# sawbench_analog_reva.net
KiCad netlist of a schematic drawn in EAGLE
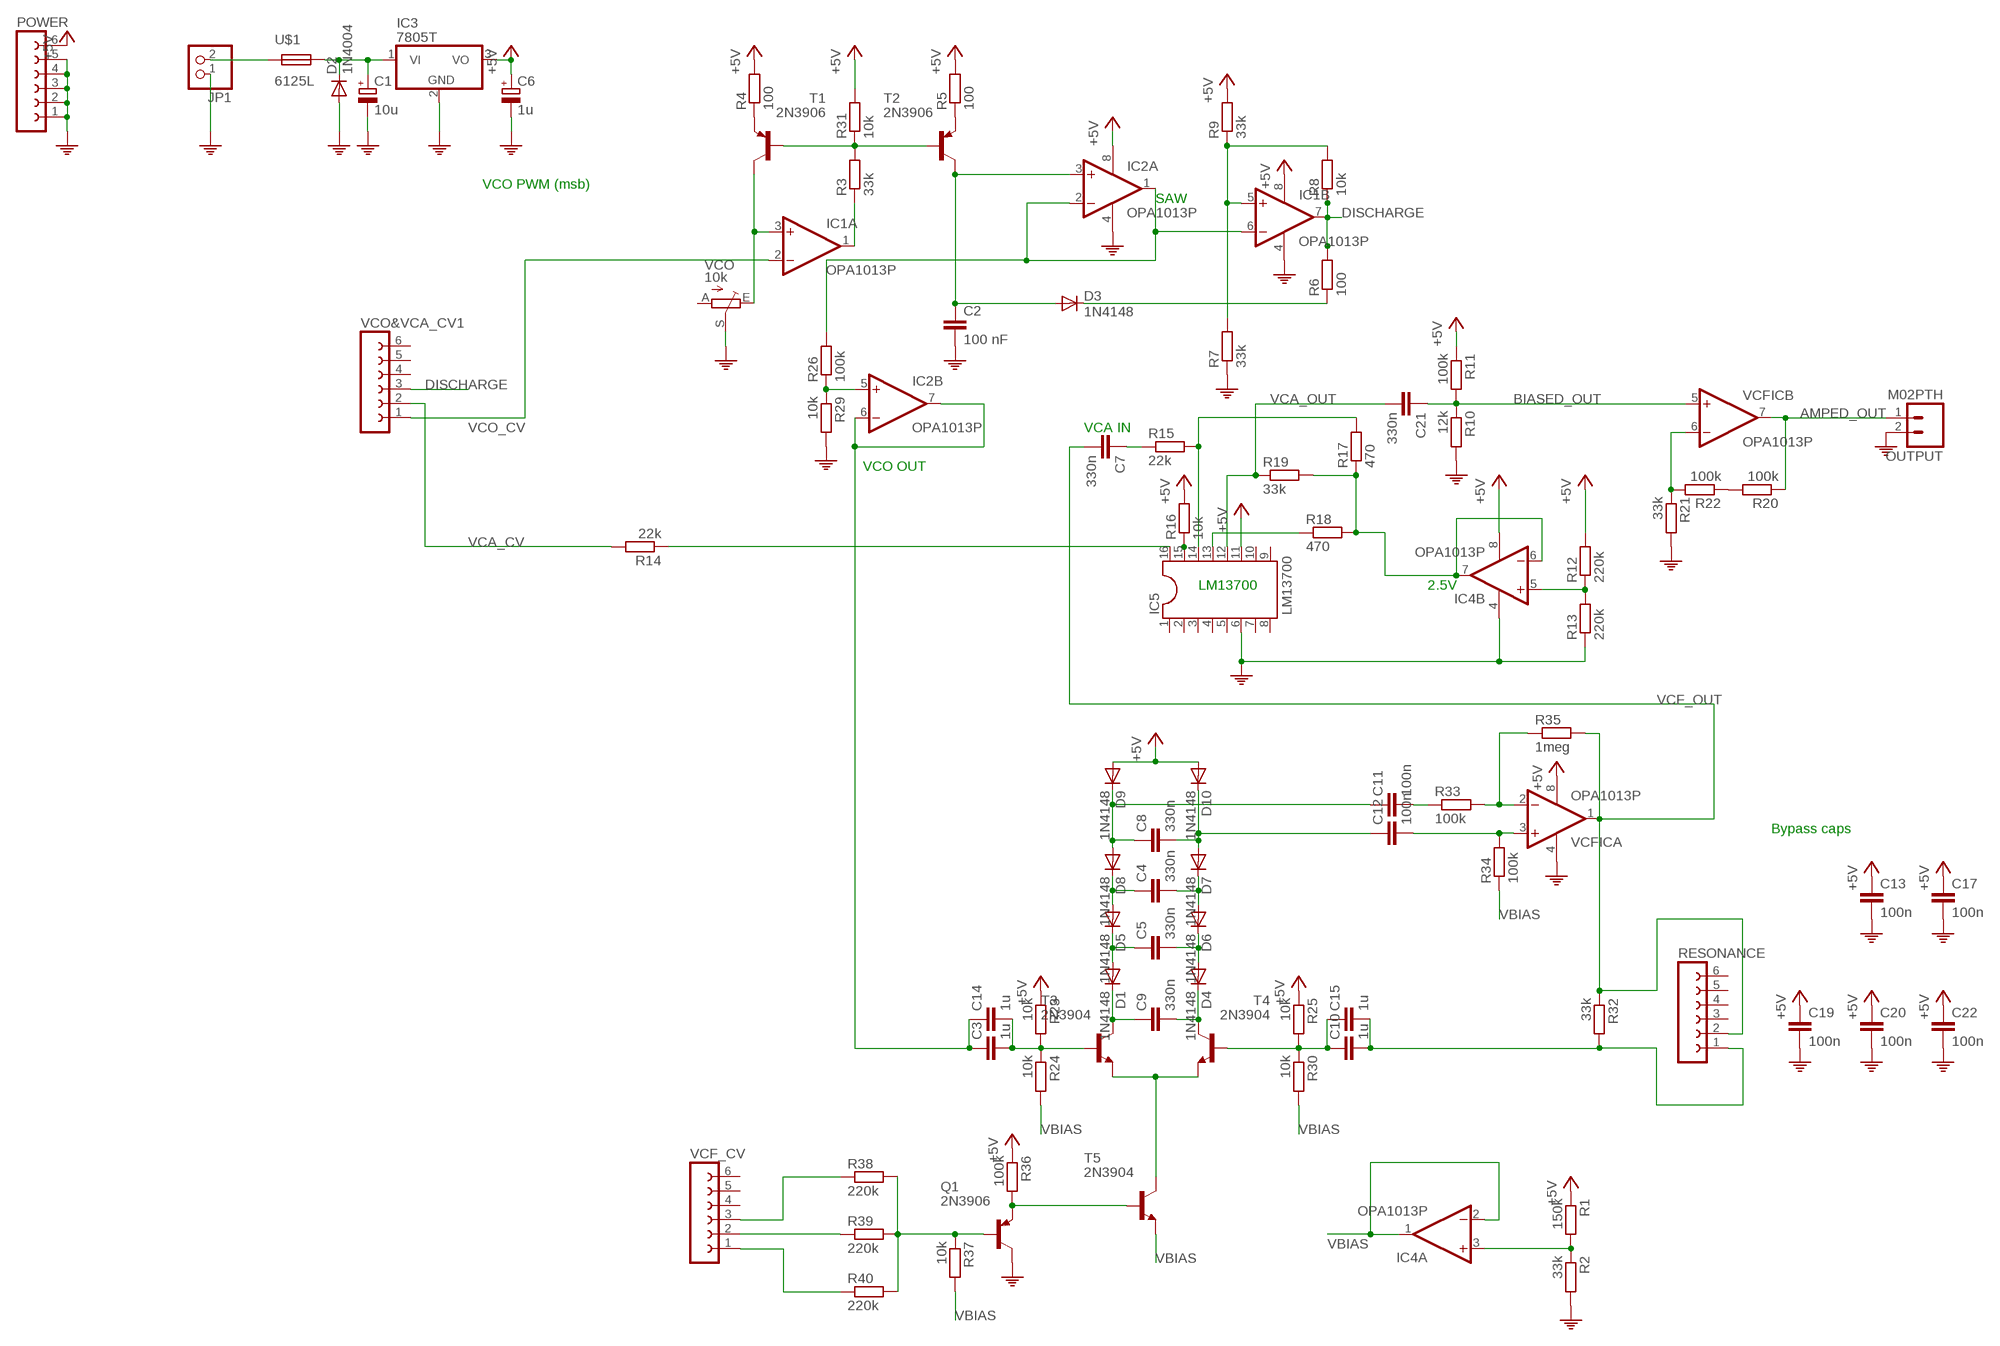
[diagram p0: schematic, sheet 1]

(export (version "E")
  (design (tool "Eeschema 10.0.6"))
  (components
    (comp (ref "C1")
      (value "10u")
      (footprint "eagle-import:E2,5-6")
      (libsource (lib "eagle-import") (part "CPOL-EUE2.5-6"))
    )
    (comp (ref "C2")
      (value "100 nF")
      (footprint "eagle-import:C050-030X075")
      (libsource (lib "eagle-import") (part "resistor_C-EU050-030X075"))
    )
    (comp (ref "C3")
      (value "1u")
      (footprint "eagle-import:C050-024X044")
      (libsource (lib "eagle-import") (part "resistor_C-EU050-024X044"))
    )
    (comp (ref "C4")
      (value "330n")
      (footprint "eagle-import:C050-030X075")
      (libsource (lib "eagle-import") (part "C-EU050-030X075"))
    )
    (comp (ref "C5")
      (value "330n")
      (footprint "eagle-import:C050-030X075")
      (libsource (lib "eagle-import") (part "C-EU050-030X075"))
    )
    (comp (ref "C6")
      (value "1u")
      (footprint "eagle-import:E2,5-6")
      (libsource (lib "eagle-import") (part "CPOL-EUE2.5-6"))
    )
    (comp (ref "C7")
      (value "330n")
      (footprint "eagle-import:C050-024X044")
      (libsource (lib "eagle-import") (part "resistor_C-EU050-024X044"))
    )
    (comp (ref "C8")
      (value "330n")
      (footprint "eagle-import:C050-030X075")
      (libsource (lib "eagle-import") (part "C-EU050-030X075"))
    )
    (comp (ref "C9")
      (value "330n")
      (footprint "eagle-import:C050-030X075")
      (libsource (lib "eagle-import") (part "C-EU050-030X075"))
    )
    (comp (ref "C10")
      (value "1u")
      (footprint "eagle-import:C050-024X044")
      (libsource (lib "eagle-import") (part "resistor_C-EU050-024X044"))
    )
    (comp (ref "C11")
      (value "100n")
      (footprint "eagle-import:C050-025X075")
      (libsource (lib "eagle-import") (part "resistor_C-EU050-025X075"))
    )
    (comp (ref "C12")
      (value "100n")
      (footprint "eagle-import:C050-025X075")
      (libsource (lib "eagle-import") (part "resistor_C-EU050-025X075"))
    )
    (comp (ref "C13")
      (value "100n")
      (footprint "eagle-import:C025-024X044")
      (libsource (lib "eagle-import") (part "resistor_C-EU025-024X044"))
    )
    (comp (ref "C14")
      (value "1u")
      (footprint "eagle-import:C050-024X044")
      (libsource (lib "eagle-import") (part "resistor_C-EU050-024X044"))
    )
    (comp (ref "C15")
      (value "1u")
      (footprint "eagle-import:C050-024X044")
      (libsource (lib "eagle-import") (part "resistor_C-EU050-024X044"))
    )
    (comp (ref "C17")
      (value "100n")
      (footprint "eagle-import:C025-024X044")
      (libsource (lib "eagle-import") (part "resistor_C-EU025-024X044"))
    )
    (comp (ref "C19")
      (value "100n")
      (footprint "eagle-import:C025-024X044")
      (libsource (lib "eagle-import") (part "resistor_C-EU025-024X044"))
    )
    (comp (ref "C20")
      (value "100n")
      (footprint "eagle-import:C025-024X044")
      (libsource (lib "eagle-import") (part "resistor_C-EU025-024X044"))
    )
    (comp (ref "C21")
      (value "330n")
      (footprint "eagle-import:C050-024X044")
      (libsource (lib "eagle-import") (part "resistor_C-EU050-024X044"))
    )
    (comp (ref "C22")
      (value "100n")
      (footprint "eagle-import:C025-024X044")
      (libsource (lib "eagle-import") (part "resistor_C-EU025-024X044"))
    )
    (comp (ref "D1")
      (value "1N4148")
      (footprint "eagle-import:D-5")
      (libsource (lib "eagle-import") (part "DIODE-D-5"))
    )
    (comp (ref "D2")
      (value "1N4004")
      (footprint "eagle-import:DO41-10")
      (libsource (lib "eagle-import") (part "1N4004"))
    )
    (comp (ref "D3")
      (value "1N4148")
      (footprint "eagle-import:D-5")
      (libsource (lib "eagle-import") (part "DIODE-D-5"))
    )
    (comp (ref "D4")
      (value "1N4148")
      (footprint "eagle-import:D-5")
      (libsource (lib "eagle-import") (part "DIODE-D-5"))
    )
    (comp (ref "D5")
      (value "1N4148")
      (footprint "eagle-import:D-5")
      (libsource (lib "eagle-import") (part "DIODE-D-5"))
    )
    (comp (ref "D6")
      (value "1N4148")
      (footprint "eagle-import:D-5")
      (libsource (lib "eagle-import") (part "DIODE-D-5"))
    )
    (comp (ref "D7")
      (value "1N4148")
      (footprint "eagle-import:D-5")
      (libsource (lib "eagle-import") (part "DIODE-D-5"))
    )
    (comp (ref "D8")
      (value "1N4148")
      (footprint "eagle-import:D-5")
      (libsource (lib "eagle-import") (part "DIODE-D-5"))
    )
    (comp (ref "D9")
      (value "1N4148")
      (footprint "eagle-import:D-5")
      (libsource (lib "eagle-import") (part "DIODE-D-5"))
    )
    (comp (ref "D10")
      (value "1N4148")
      (footprint "eagle-import:D-5")
      (libsource (lib "eagle-import") (part "DIODE-D-5"))
    )
    (comp (ref "IC1")
      (value "OPA1013P")
      (footprint "eagle-import:DIL08")
      (libsource (lib "eagle-import") (part "OPA1013P"))
    )
    (comp (ref "IC2")
      (value "OPA1013P")
      (footprint "eagle-import:DIL08")
      (libsource (lib "eagle-import") (part "OPA1013P"))
    )
    (comp (ref "IC3")
      (value "7805T")
      (footprint "eagle-import:TO220H")
      (libsource (lib "eagle-import") (part "78T05"))
    )
    (comp (ref "IC4")
      (value "OPA1013P")
      (footprint "eagle-import:DIL08")
      (libsource (lib "eagle-import") (part "OPA1013P"))
    )
    (comp (ref "IC5")
      (value "LM13700")
      (footprint "eagle-import:DIL16")
      (libsource (lib "eagle-import") (part "DIL16"))
    )
    (comp (ref "JP1")
      (value "PINHD-1X2")
      (footprint "eagle-import:1X02")
      (libsource (lib "eagle-import") (part "PINHD-1X2"))
    )
    (comp (ref "OUTPUT")
      (value "M02PTH")
      (footprint "eagle-import:1X02")
      (libsource (lib "eagle-import") (part "M02PTH"))
    )
    (comp (ref "POWER")
      (value "FE06-1")
      (footprint "eagle-import:FE06")
      (libsource (lib "eagle-import") (part "FE06-1"))
    )
    (comp (ref "Q1")
      (value "2N3906")
      (footprint "eagle-import:TO92-EBC")
      (libsource (lib "eagle-import") (part "-PNP-TO92-EBC2N3906"))
    )
    (comp (ref "R1")
      (value "150k")
      (footprint "eagle-import:0204_7")
      (libsource (lib "eagle-import") (part "R-EU_0204/7"))
    )
    (comp (ref "R2")
      (value "33k")
      (footprint "eagle-import:0204_7")
      (libsource (lib "eagle-import") (part "R-EU_0204/7"))
    )
    (comp (ref "R3")
      (value "33k")
      (footprint "eagle-import:0204_7")
      (libsource (lib "eagle-import") (part "R-EU_0204/7"))
    )
    (comp (ref "R4")
      (value "100")
      (footprint "eagle-import:0204_7")
      (libsource (lib "eagle-import") (part "R-EU_0204/7"))
    )
    (comp (ref "R5")
      (value "100")
      (footprint "eagle-import:0204_7")
      (libsource (lib "eagle-import") (part "R-EU_0204/7"))
    )
    (comp (ref "R6")
      (value "100")
      (footprint "eagle-import:0204_7")
      (libsource (lib "eagle-import") (part "R-EU_0204/7"))
    )
    (comp (ref "R7")
      (value "33k")
      (footprint "eagle-import:0204_7")
      (libsource (lib "eagle-import") (part "R-EU_0204/7"))
    )
    (comp (ref "R8")
      (value "10k")
      (footprint "eagle-import:0204_7")
      (libsource (lib "eagle-import") (part "R-EU_0204/7"))
    )
    (comp (ref "R9")
      (value "33k")
      (footprint "eagle-import:0204_7")
      (libsource (lib "eagle-import") (part "R-EU_0204/7"))
    )
    (comp (ref "R10")
      (value "12k")
      (footprint "eagle-import:0204_7")
      (libsource (lib "eagle-import") (part "R-EU_0204/7"))
    )
    (comp (ref "R11")
      (value "100k")
      (footprint "eagle-import:0204_7")
      (libsource (lib "eagle-import") (part "R-EU_0204/7"))
    )
    (comp (ref "R12")
      (value "220k")
      (footprint "eagle-import:0204_7")
      (libsource (lib "eagle-import") (part "R-EU_0204/7"))
    )
    (comp (ref "R13")
      (value "220k")
      (footprint "eagle-import:0204_7")
      (libsource (lib "eagle-import") (part "R-EU_0204/7"))
    )
    (comp (ref "R14")
      (value "22k")
      (footprint "eagle-import:0204_7")
      (libsource (lib "eagle-import") (part "R-EU_0204/7"))
    )
    (comp (ref "R15")
      (value "22k")
      (footprint "eagle-import:0204_7")
      (libsource (lib "eagle-import") (part "R-EU_0204/7"))
    )
    (comp (ref "R16")
      (value "10k")
      (footprint "eagle-import:0204_7")
      (libsource (lib "eagle-import") (part "R-EU_0204/7"))
    )
    (comp (ref "R17")
      (value "470")
      (footprint "eagle-import:0204_7")
      (libsource (lib "eagle-import") (part "R-EU_0204/7"))
    )
    (comp (ref "R18")
      (value "470")
      (footprint "eagle-import:0204_7")
      (libsource (lib "eagle-import") (part "R-EU_0204/7"))
    )
    (comp (ref "R19")
      (value "33k")
      (footprint "eagle-import:0204_7")
      (libsource (lib "eagle-import") (part "R-EU_0204/7"))
    )
    (comp (ref "R20")
      (value "100k")
      (footprint "eagle-import:0204_7")
      (libsource (lib "eagle-import") (part "R-EU_0204/7"))
    )
    (comp (ref "R21")
      (value "33k")
      (footprint "eagle-import:0204_7")
      (libsource (lib "eagle-import") (part "R-EU_0204/7"))
    )
    (comp (ref "R22")
      (value "100k")
      (footprint "eagle-import:0204_7")
      (libsource (lib "eagle-import") (part "R-EU_0204/7"))
    )
    (comp (ref "R23")
      (value "10k")
      (footprint "eagle-import:0204_7")
      (libsource (lib "eagle-import") (part "R-EU_0204/7"))
    )
    (comp (ref "R24")
      (value "10k")
      (footprint "eagle-import:0204_7")
      (libsource (lib "eagle-import") (part "R-EU_0204/7"))
    )
    (comp (ref "R25")
      (value "10k")
      (footprint "eagle-import:0204_7")
      (libsource (lib "eagle-import") (part "R-EU_0204/7"))
    )
    (comp (ref "R26")
      (value "100k")
      (footprint "eagle-import:0204_7")
      (libsource (lib "eagle-import") (part "R-EU_0204/7"))
    )
    (comp (ref "R29")
      (value "10k")
      (footprint "eagle-import:0204_7")
      (libsource (lib "eagle-import") (part "R-EU_0204/7"))
    )
    (comp (ref "R30")
      (value "10k")
      (footprint "eagle-import:0204_7")
      (libsource (lib "eagle-import") (part "R-EU_0204/7"))
    )
    (comp (ref "R31")
      (value "10k")
      (footprint "eagle-import:0204_7")
      (libsource (lib "eagle-import") (part "R-EU_0204/7"))
    )
    (comp (ref "R32")
      (value "33k")
      (footprint "eagle-import:0204_7")
      (libsource (lib "eagle-import") (part "R-EU_0204/7"))
    )
    (comp (ref "R33")
      (value "100k")
      (footprint "eagle-import:0204_7")
      (libsource (lib "eagle-import") (part "R-EU_0204/7"))
    )
    (comp (ref "R34")
      (value "100k")
      (footprint "eagle-import:0204_7")
      (libsource (lib "eagle-import") (part "R-EU_0204/7"))
    )
    (comp (ref "R35")
      (value "1meg")
      (footprint "eagle-import:0204_7")
      (libsource (lib "eagle-import") (part "R-EU_0204/7"))
    )
    (comp (ref "R36")
      (value "100k")
      (footprint "eagle-import:0204_7")
      (libsource (lib "eagle-import") (part "R-EU_0204/7"))
    )
    (comp (ref "R37")
      (value "10k")
      (footprint "eagle-import:0204_7")
      (libsource (lib "eagle-import") (part "R-EU_0204/7"))
    )
    (comp (ref "R38")
      (value "220k")
      (footprint "eagle-import:0204_7")
      (libsource (lib "eagle-import") (part "R-EU_0204/7"))
    )
    (comp (ref "R39")
      (value "220k")
      (footprint "eagle-import:0204_7")
      (libsource (lib "eagle-import") (part "R-EU_0204/7"))
    )
    (comp (ref "R40")
      (value "220k")
      (footprint "eagle-import:0204_7")
      (libsource (lib "eagle-import") (part "R-EU_0204/7"))
    )
    (comp (ref "RESONANCE")
      (value "FE06-1")
      (footprint "eagle-import:FE06")
      (libsource (lib "eagle-import") (part "FE06-1"))
    )
    (comp (ref "T1")
      (value "2N3906")
      (footprint "eagle-import:TO92-EBC")
      (libsource (lib "eagle-import") (part "-PNP-TO92-EBC2N3906"))
    )
    (comp (ref "T2")
      (value "2N3906")
      (footprint "eagle-import:TO92-EBC")
      (libsource (lib "eagle-import") (part "-PNP-TO92-EBC2N3906"))
    )
    (comp (ref "T3")
      (value "2N3904")
      (footprint "eagle-import:TO92-EBC")
      (libsource (lib "eagle-import") (part "-NPN-TO92-EBC2N3904"))
    )
    (comp (ref "T4")
      (value "2N3904")
      (footprint "eagle-import:TO92-EBC")
      (libsource (lib "eagle-import") (part "-NPN-TO92-EBC2N3904"))
    )
    (comp (ref "T5")
      (value "2N3904")
      (footprint "eagle-import:TO92-EBC")
      (libsource (lib "eagle-import") (part "-NPN-TO92-EBC2N3904"))
    )
    (comp (ref "U$1")
      (value "6125L")
      (footprint "eagle-import:6125L")
      (libsource (lib "eagle-import") (part "6125L"))
    )
    (comp (ref "VCFIC")
      (value "OPA1013P")
      (footprint "eagle-import:DIL08")
      (libsource (lib "eagle-import") (part "OPA1013P"))
    )
    (comp (ref "VCF_CV")
      (value "FE06-1")
      (footprint "eagle-import:FE06")
      (libsource (lib "eagle-import") (part "FE06-1"))
    )
    (comp (ref "VCO")
      (value "10k")
      (footprint "eagle-import:RJ9W")
      (libsource (lib "eagle-import") (part "TRIM_EU-RJ9W"))
    )
    (comp (ref "VCO&VCA_CV1")
      (value "FE06-1")
      (footprint "eagle-import:FE06")
      (libsource (lib "eagle-import") (part "FE06-1"))
    )
  )
  (nets
    (net (code "1") (name "+5V") (class "Default")
      (node (ref "C13") (pin "1") (pinfunction "1_1") (pintype "passive"))
      (node (ref "C17") (pin "1") (pinfunction "1_1") (pintype "passive"))
      (node (ref "C19") (pin "1") (pinfunction "1_1") (pintype "passive"))
      (node (ref "C20") (pin "1") (pinfunction "1_1") (pintype "passive"))
      (node (ref "C22") (pin "1") (pinfunction "1_1") (pintype "passive"))
      (node (ref "C6") (pin "+") (pinfunction "+_+") (pintype "passive"))
      (node (ref "D10") (pin "A") (pinfunction "A_A") (pintype "passive"))
      (node (ref "D9") (pin "A") (pinfunction "A_A") (pintype "passive"))
      (node (ref "IC1") (pin "8") (pinfunction "V+_8") (pintype "power_in"))
      (node (ref "IC2") (pin "8") (pinfunction "V+_8") (pintype "power_in"))
      (node (ref "IC3") (pin "3") (pinfunction "VO_3") (pintype "passive"))
      (node (ref "IC4") (pin "8") (pinfunction "V+_8") (pintype "power_in"))
      (node (ref "IC5") (pin "11") (pinfunction "11_11") (pintype "passive"))
      (node (ref "POWER") (pin "6") (pinfunction "6_6") (pintype "passive"))
      (node (ref "R1") (pin "1") (pinfunction "1_1") (pintype "passive"))
      (node (ref "R11") (pin "1") (pinfunction "1_1") (pintype "passive"))
      (node (ref "R12") (pin "2") (pinfunction "2_2") (pintype "passive"))
      (node (ref "R16") (pin "2") (pinfunction "2_2") (pintype "passive"))
      (node (ref "R23") (pin "1") (pinfunction "1_1") (pintype "passive"))
      (node (ref "R25") (pin "1") (pinfunction "1_1") (pintype "passive"))
      (node (ref "R31") (pin "2") (pinfunction "2_2") (pintype "passive"))
      (node (ref "R36") (pin "1") (pinfunction "1_1") (pintype "passive"))
      (node (ref "R4") (pin "2") (pinfunction "2_2") (pintype "passive"))
      (node (ref "R5") (pin "2") (pinfunction "2_2") (pintype "passive"))
      (node (ref "R9") (pin "2") (pinfunction "2_2") (pintype "passive"))
      (node (ref "VCFIC") (pin "8") (pinfunction "V+_8") (pintype "power_in"))
    )
    (net (code "2") (name "/AMPED_OUT") (class "Default")
      (node (ref "OUTPUT") (pin "1") (pinfunction "1_1") (pintype "passive"))
      (node (ref "R20") (pin "1") (pinfunction "1_1") (pintype "passive"))
      (node (ref "VCFIC") (pin "7") (pinfunction "OUT_7") (pintype "output"))
    )
    (net (code "3") (name "/BIASED_OUT") (class "Default")
      (node (ref "C21") (pin "1") (pinfunction "1_1") (pintype "passive"))
      (node (ref "R10") (pin "1") (pinfunction "1_1") (pintype "passive"))
      (node (ref "R11") (pin "2") (pinfunction "2_2") (pintype "passive"))
      (node (ref "VCFIC") (pin "5") (pinfunction "+IN_5") (pintype "input"))
    )
    (net (code "4") (name "/DISCHARGE") (class "Default")
      (node (ref "IC1") (pin "7") (pinfunction "OUT_7") (pintype "output"))
      (node (ref "R6") (pin "2") (pinfunction "2_2") (pintype "passive"))
      (node (ref "R8") (pin "1") (pinfunction "1_1") (pintype "passive"))
      (node (ref "VCO&VCA_CV1") (pin "3") (pinfunction "3_3") (pintype "passive"))
    )
    (net (code "5") (name "/VBIAS") (class "Default")
      (node (ref "IC4") (pin "1") (pinfunction "OUT_1") (pintype "output"))
      (node (ref "IC4") (pin "2") (pinfunction "-IN_2") (pintype "input"))
      (node (ref "R24") (pin "2") (pinfunction "2_2") (pintype "passive"))
      (node (ref "R30") (pin "2") (pinfunction "2_2") (pintype "passive"))
      (node (ref "R34") (pin "1") (pinfunction "1_1") (pintype "passive"))
      (node (ref "R37") (pin "2") (pinfunction "2_2") (pintype "passive"))
      (node (ref "T5") (pin "E") (pinfunction "E_E") (pintype "passive"))
    )
    (net (code "6") (name "/VCA_CV") (class "Default")
      (node (ref "R14") (pin "2") (pinfunction "2_2") (pintype "passive"))
      (node (ref "VCO&VCA_CV1") (pin "2") (pinfunction "2_2") (pintype "passive"))
    )
    (net (code "7") (name "/VCA_OUT") (class "Default")
      (node (ref "C21") (pin "2") (pinfunction "2_2") (pintype "passive"))
      (node (ref "IC5") (pin "12") (pinfunction "12_12") (pintype "passive"))
      (node (ref "R19") (pin "1") (pinfunction "1_1") (pintype "passive"))
    )
    (net (code "8") (name "/VCF_OUT") (class "Default")
      (node (ref "C7") (pin "2") (pinfunction "2_2") (pintype "passive"))
      (node (ref "R32") (pin "1") (pinfunction "1_1") (pintype "passive"))
      (node (ref "R35") (pin "2") (pinfunction "2_2") (pintype "passive"))
      (node (ref "RESONANCE") (pin "2") (pinfunction "2_2") (pintype "passive"))
      (node (ref "VCFIC") (pin "1") (pinfunction "OUT_1") (pintype "output"))
    )
    (net (code "9") (name "/VCO_CV") (class "Default")
      (node (ref "IC1") (pin "2") (pinfunction "-IN_2") (pintype "input"))
      (node (ref "VCO&VCA_CV1") (pin "1") (pinfunction "1_1") (pintype "passive"))
    )
    (net (code "10") (name "Net-(C4-Pad1)") (class "Default")
      (node (ref "C4") (pin "1") (pinfunction "1_1") (pintype "passive"))
      (node (ref "D5") (pin "A") (pinfunction "A_A") (pintype "passive"))
      (node (ref "D8") (pin "C") (pinfunction "C_C") (pintype "passive"))
    )
    (net (code "11") (name "Net-(C4-Pad2)") (class "Default")
      (node (ref "C4") (pin "2") (pinfunction "2_2") (pintype "passive"))
      (node (ref "D6") (pin "A") (pinfunction "A_A") (pintype "passive"))
      (node (ref "D7") (pin "C") (pinfunction "C_C") (pintype "passive"))
    )
    (net (code "12") (name "Net-(C5-Pad1)") (class "Default")
      (node (ref "C5") (pin "1") (pinfunction "1_1") (pintype "passive"))
      (node (ref "D1") (pin "A") (pinfunction "A_A") (pintype "passive"))
      (node (ref "D5") (pin "C") (pinfunction "C_C") (pintype "passive"))
    )
    (net (code "13") (name "Net-(C5-Pad2)") (class "Default")
      (node (ref "C5") (pin "2") (pinfunction "2_2") (pintype "passive"))
      (node (ref "D4") (pin "A") (pinfunction "A_A") (pintype "passive"))
      (node (ref "D6") (pin "C") (pinfunction "C_C") (pintype "passive"))
    )
    (net (code "14") (name "Net-(C7-Pad1)") (class "Default")
      (node (ref "C7") (pin "1") (pinfunction "1_1") (pintype "passive"))
      (node (ref "R15") (pin "1") (pinfunction "1_1") (pintype "passive"))
    )
    (net (code "15") (name "Net-(C9-Pad1)") (class "Default")
      (node (ref "C9") (pin "1") (pinfunction "1_1") (pintype "passive"))
      (node (ref "D1") (pin "C") (pinfunction "C_C") (pintype "passive"))
      (node (ref "T3") (pin "C") (pinfunction "C_C") (pintype "passive"))
    )
    (net (code "16") (name "Net-(C9-Pad2)") (class "Default")
      (node (ref "C9") (pin "2") (pinfunction "2_2") (pintype "passive"))
      (node (ref "D4") (pin "C") (pinfunction "C_C") (pintype "passive"))
      (node (ref "T4") (pin "C") (pinfunction "C_C") (pintype "passive"))
    )
    (net (code "17") (name "Net-(C10-Pad1)") (class "Default")
      (node (ref "C10") (pin "1") (pinfunction "1_1") (pintype "passive"))
      (node (ref "C15") (pin "1") (pinfunction "1_1") (pintype "passive"))
      (node (ref "R25") (pin "2") (pinfunction "2_2") (pintype "passive"))
      (node (ref "R30") (pin "1") (pinfunction "1_1") (pintype "passive"))
      (node (ref "T4") (pin "B") (pinfunction "B_B") (pintype "passive"))
    )
    (net (code "18") (name "Net-(C10-Pad2)") (class "Default")
      (node (ref "C10") (pin "2") (pinfunction "2_2") (pintype "passive"))
      (node (ref "C15") (pin "2") (pinfunction "2_2") (pintype "passive"))
      (node (ref "R32") (pin "2") (pinfunction "2_2") (pintype "passive"))
      (node (ref "RESONANCE") (pin "1") (pinfunction "1_1") (pintype "passive"))
    )
    (net (code "19") (name "Net-(C11-Pad1)") (class "Default")
      (node (ref "C11") (pin "1") (pinfunction "1_1") (pintype "passive"))
      (node (ref "C8") (pin "1") (pinfunction "1_1") (pintype "passive"))
      (node (ref "D8") (pin "A") (pinfunction "A_A") (pintype "passive"))
      (node (ref "D9") (pin "C") (pinfunction "C_C") (pintype "passive"))
    )
    (net (code "20") (name "Net-(C11-Pad2)") (class "Default")
      (node (ref "C11") (pin "2") (pinfunction "2_2") (pintype "passive"))
      (node (ref "R33") (pin "1") (pinfunction "1_1") (pintype "passive"))
    )
    (net (code "21") (name "Net-(C12-Pad1)") (class "Default")
      (node (ref "C12") (pin "1") (pinfunction "1_1") (pintype "passive"))
      (node (ref "C8") (pin "2") (pinfunction "2_2") (pintype "passive"))
      (node (ref "D10") (pin "C") (pinfunction "C_C") (pintype "passive"))
      (node (ref "D7") (pin "A") (pinfunction "A_A") (pintype "passive"))
    )
    (net (code "22") (name "Net-(C14-Pad2)") (class "Default")
      (node (ref "C14") (pin "2") (pinfunction "2_2") (pintype "passive"))
      (node (ref "C3") (pin "2") (pinfunction "2_2") (pintype "passive"))
      (node (ref "R23") (pin "2") (pinfunction "2_2") (pintype "passive"))
      (node (ref "R24") (pin "1") (pinfunction "1_1") (pintype "passive"))
      (node (ref "T3") (pin "B") (pinfunction "B_B") (pintype "passive"))
    )
    (net (code "23") (name "Net-(D3-PadC)") (class "Default")
      (node (ref "D3") (pin "C") (pinfunction "C_C") (pintype "passive"))
      (node (ref "R6") (pin "1") (pinfunction "1_1") (pintype "passive"))
    )
    (net (code "24") (name "Net-(IC1A-+IN)") (class "Default")
      (node (ref "IC1") (pin "3") (pinfunction "+IN_3") (pintype "input"))
      (node (ref "T1") (pin "C") (pinfunction "C_C") (pintype "passive"))
      (node (ref "VCO") (pin "E") (pinfunction "E_E") (pintype "passive"))
    )
    (net (code "25") (name "Net-(IC1A-OUT)") (class "Default")
      (node (ref "IC1") (pin "1") (pinfunction "OUT_1") (pintype "output"))
      (node (ref "R3") (pin "1") (pinfunction "1_1") (pintype "passive"))
    )
    (net (code "26") (name "Net-(IC1B-+IN)") (class "Default")
      (node (ref "IC1") (pin "5") (pinfunction "+IN_5") (pintype "input"))
      (node (ref "R7") (pin "2") (pinfunction "2_2") (pintype "passive"))
      (node (ref "R8") (pin "2") (pinfunction "2_2") (pintype "passive"))
      (node (ref "R9") (pin "1") (pinfunction "1_1") (pintype "passive"))
    )
    (net (code "27") (name "Net-(IC1B--IN)") (class "Default")
      (node (ref "IC1") (pin "6") (pinfunction "-IN_6") (pintype "input"))
      (node (ref "IC2") (pin "1") (pinfunction "OUT_1") (pintype "output"))
      (node (ref "IC2") (pin "2") (pinfunction "-IN_2") (pintype "input"))
      (node (ref "R26") (pin "2") (pinfunction "2_2") (pintype "passive"))
    )
    (net (code "28") (name "Net-(IC2A-+IN)") (class "Default")
      (node (ref "C2") (pin "1") (pinfunction "1_1") (pintype "passive"))
      (node (ref "D3") (pin "A") (pinfunction "A_A") (pintype "passive"))
      (node (ref "IC2") (pin "3") (pinfunction "+IN_3") (pintype "input"))
      (node (ref "T2") (pin "C") (pinfunction "C_C") (pintype "passive"))
    )
    (net (code "29") (name "Net-(IC2B-+IN)") (class "Default")
      (node (ref "IC2") (pin "5") (pinfunction "+IN_5") (pintype "input"))
      (node (ref "R26") (pin "1") (pinfunction "1_1") (pintype "passive"))
      (node (ref "R29") (pin "1") (pinfunction "1_1") (pintype "passive"))
    )
    (net (code "30") (name "Net-(IC2B--IN)") (class "Default")
      (node (ref "C14") (pin "1") (pinfunction "1_1") (pintype "passive"))
      (node (ref "C3") (pin "1") (pinfunction "1_1") (pintype "passive"))
      (node (ref "IC2") (pin "6") (pinfunction "-IN_6") (pintype "input"))
      (node (ref "IC2") (pin "7") (pinfunction "OUT_7") (pintype "output"))
    )
    (net (code "31") (name "Net-(IC3-VI)") (class "Default")
      (node (ref "C1") (pin "+") (pinfunction "+_+") (pintype "passive"))
      (node (ref "D2") (pin "C") (pinfunction "C_C") (pintype "passive"))
      (node (ref "IC3") (pin "1") (pinfunction "VI_1") (pintype "input"))
      (node (ref "U$1") (pin "P$2") (pinfunction "2_P$2") (pintype "passive"))
    )
    (net (code "32") (name "Net-(IC4A-+IN)") (class "Default")
      (node (ref "IC4") (pin "3") (pinfunction "+IN_3") (pintype "input"))
      (node (ref "R1") (pin "2") (pinfunction "2_2") (pintype "passive"))
      (node (ref "R2") (pin "1") (pinfunction "1_1") (pintype "passive"))
    )
    (net (code "33") (name "Net-(IC4B-+IN)") (class "Default")
      (node (ref "IC4") (pin "5") (pinfunction "+IN_5") (pintype "input"))
      (node (ref "R12") (pin "1") (pinfunction "1_1") (pintype "passive"))
      (node (ref "R13") (pin "2") (pinfunction "2_2") (pintype "passive"))
    )
    (net (code "34") (name "Net-(IC4B--IN)") (class "Default")
      (node (ref "IC4") (pin "6") (pinfunction "-IN_6") (pintype "input"))
      (node (ref "IC4") (pin "7") (pinfunction "OUT_7") (pintype "output"))
      (node (ref "R17") (pin "1") (pinfunction "1_1") (pintype "passive"))
      (node (ref "R18") (pin "2") (pinfunction "2_2") (pintype "passive"))
      (node (ref "R19") (pin "2") (pinfunction "2_2") (pintype "passive"))
    )
    (net (code "35") (name "Net-(IC5-Pad13)") (class "Default")
      (node (ref "IC5") (pin "13") (pinfunction "13_13") (pintype "passive"))
      (node (ref "R18") (pin "1") (pinfunction "1_1") (pintype "passive"))
    )
    (net (code "36") (name "Net-(IC5-Pad14)") (class "Default")
      (node (ref "IC5") (pin "14") (pinfunction "14_14") (pintype "passive"))
      (node (ref "R15") (pin "2") (pinfunction "2_2") (pintype "passive"))
      (node (ref "R17") (pin "2") (pinfunction "2_2") (pintype "passive"))
    )
    (net (code "37") (name "Net-(IC5-Pad15)") (class "Default")
      (node (ref "IC5") (pin "15") (pinfunction "15_15") (pintype "passive"))
      (node (ref "R16") (pin "1") (pinfunction "1_1") (pintype "passive"))
    )
    (net (code "38") (name "Net-(IC5-Pad16)") (class "Default")
      (node (ref "IC5") (pin "16") (pinfunction "16_16") (pintype "passive"))
      (node (ref "R14") (pin "1") (pinfunction "1_1") (pintype "passive"))
    )
    (net (code "39") (name "Net-(Q1-PadB)") (class "Default")
      (node (ref "Q1") (pin "B") (pinfunction "B_B") (pintype "passive"))
      (node (ref "R37") (pin "1") (pinfunction "1_1") (pintype "passive"))
      (node (ref "R38") (pin "2") (pinfunction "2_2") (pintype "passive"))
      (node (ref "R39") (pin "2") (pinfunction "2_2") (pintype "passive"))
      (node (ref "R40") (pin "2") (pinfunction "2_2") (pintype "passive"))
    )
    (net (code "40") (name "Net-(Q1-PadE)") (class "Default")
      (node (ref "Q1") (pin "E") (pinfunction "E_E") (pintype "passive"))
      (node (ref "R36") (pin "2") (pinfunction "2_2") (pintype "passive"))
      (node (ref "T5") (pin "B") (pinfunction "B_B") (pintype "passive"))
    )
    (net (code "41") (name "Net-(R3-Pad2)") (class "Default")
      (node (ref "R3") (pin "2") (pinfunction "2_2") (pintype "passive"))
      (node (ref "R31") (pin "1") (pinfunction "1_1") (pintype "passive"))
      (node (ref "T1") (pin "B") (pinfunction "B_B") (pintype "passive"))
      (node (ref "T2") (pin "B") (pinfunction "B_B") (pintype "passive"))
    )
    (net (code "42") (name "Net-(R4-Pad1)") (class "Default")
      (node (ref "R4") (pin "1") (pinfunction "1_1") (pintype "passive"))
      (node (ref "T1") (pin "E") (pinfunction "E_E") (pintype "passive"))
    )
    (net (code "43") (name "Net-(R5-Pad1)") (class "Default")
      (node (ref "R5") (pin "1") (pinfunction "1_1") (pintype "passive"))
      (node (ref "T2") (pin "E") (pinfunction "E_E") (pintype "passive"))
    )
    (net (code "44") (name "Net-(R20-Pad2)") (class "Default")
      (node (ref "R20") (pin "2") (pinfunction "2_2") (pintype "passive"))
      (node (ref "R22") (pin "1") (pinfunction "1_1") (pintype "passive"))
    )
    (net (code "45") (name "Net-(R38-Pad1)") (class "Default")
      (node (ref "R38") (pin "1") (pinfunction "1_1") (pintype "passive"))
      (node (ref "VCF_CV") (pin "3") (pinfunction "3_3") (pintype "passive"))
    )
    (net (code "46") (name "Net-(R39-Pad1)") (class "Default")
      (node (ref "R39") (pin "1") (pinfunction "1_1") (pintype "passive"))
      (node (ref "VCF_CV") (pin "2") (pinfunction "2_2") (pintype "passive"))
    )
    (net (code "47") (name "Net-(R40-Pad1)") (class "Default")
      (node (ref "R40") (pin "1") (pinfunction "1_1") (pintype "passive"))
      (node (ref "VCF_CV") (pin "1") (pinfunction "1_1") (pintype "passive"))
    )
    (net (code "48") (name "Net-(T3-PadE)") (class "Default")
      (node (ref "T3") (pin "E") (pinfunction "E_E") (pintype "passive"))
      (node (ref "T4") (pin "E") (pinfunction "E_E") (pintype "passive"))
      (node (ref "T5") (pin "C") (pinfunction "C_C") (pintype "passive"))
    )
    (net (code "49") (name "Net-(U$1-1)") (class "Default")
      (node (ref "JP1") (pin "2") (pinfunction "2_2") (pintype "passive"))
      (node (ref "U$1") (pin "P$1") (pinfunction "1_P$1") (pintype "passive"))
    )
    (net (code "50") (name "Net-(VCFICA-+IN)") (class "Default")
      (node (ref "C12") (pin "2") (pinfunction "2_2") (pintype "passive"))
      (node (ref "R34") (pin "2") (pinfunction "2_2") (pintype "passive"))
      (node (ref "VCFIC") (pin "3") (pinfunction "+IN_3") (pintype "input"))
    )
    (net (code "51") (name "Net-(VCFICA--IN)") (class "Default")
      (node (ref "R33") (pin "2") (pinfunction "2_2") (pintype "passive"))
      (node (ref "R35") (pin "1") (pinfunction "1_1") (pintype "passive"))
      (node (ref "VCFIC") (pin "2") (pinfunction "-IN_2") (pintype "input"))
    )
    (net (code "52") (name "Net-(VCFICB--IN)") (class "Default")
      (node (ref "R21") (pin "1") (pinfunction "1_1") (pintype "passive"))
      (node (ref "R22") (pin "2") (pinfunction "2_2") (pintype "passive"))
      (node (ref "VCFIC") (pin "6") (pinfunction "-IN_6") (pintype "input"))
    )
    (net (code "53") (name "PE") (class "Default")
      (node (ref "C1") (pin "-") (pinfunction "-_-") (pintype "passive"))
      (node (ref "C13") (pin "2") (pinfunction "2_2") (pintype "passive"))
      (node (ref "C17") (pin "2") (pinfunction "2_2") (pintype "passive"))
      (node (ref "C19") (pin "2") (pinfunction "2_2") (pintype "passive"))
      (node (ref "C2") (pin "2") (pinfunction "2_2") (pintype "passive"))
      (node (ref "C20") (pin "2") (pinfunction "2_2") (pintype "passive"))
      (node (ref "C22") (pin "2") (pinfunction "2_2") (pintype "passive"))
      (node (ref "C6") (pin "-") (pinfunction "-_-") (pintype "passive"))
      (node (ref "D2") (pin "A") (pinfunction "A_A") (pintype "passive"))
      (node (ref "IC1") (pin "4") (pinfunction "V-_4") (pintype "power_in"))
      (node (ref "IC2") (pin "4") (pinfunction "V-_4") (pintype "power_in"))
      (node (ref "IC3") (pin "2") (pinfunction "GND_2") (pintype "passive"))
      (node (ref "IC4") (pin "4") (pinfunction "V-_4") (pintype "power_in"))
      (node (ref "IC5") (pin "6") (pinfunction "6_6") (pintype "passive"))
      (node (ref "JP1") (pin "1") (pinfunction "1_1") (pintype "passive"))
      (node (ref "OUTPUT") (pin "2") (pinfunction "2_2") (pintype "passive"))
      (node (ref "POWER") (pin "1") (pinfunction "1_1") (pintype "passive"))
      (node (ref "POWER") (pin "2") (pinfunction "2_2") (pintype "passive"))
      (node (ref "POWER") (pin "3") (pinfunction "3_3") (pintype "passive"))
      (node (ref "POWER") (pin "4") (pinfunction "4_4") (pintype "passive"))
      (node (ref "POWER") (pin "5") (pinfunction "5_5") (pintype "passive"))
      (node (ref "Q1") (pin "C") (pinfunction "C_C") (pintype "passive"))
      (node (ref "R10") (pin "2") (pinfunction "2_2") (pintype "passive"))
      (node (ref "R13") (pin "1") (pinfunction "1_1") (pintype "passive"))
      (node (ref "R2") (pin "2") (pinfunction "2_2") (pintype "passive"))
      (node (ref "R21") (pin "2") (pinfunction "2_2") (pintype "passive"))
      (node (ref "R29") (pin "2") (pinfunction "2_2") (pintype "passive"))
      (node (ref "R7") (pin "1") (pinfunction "1_1") (pintype "passive"))
      (node (ref "VCFIC") (pin "4") (pinfunction "V-_4") (pintype "power_in"))
      (node (ref "VCO") (pin "S") (pinfunction "S_S") (pintype "passive"))
    )
    (net (code "54") (name "unconnected-(IC5-Pad1)") (class "Default")
      (node (ref "IC5") (pin "1") (pinfunction "1_1") (pintype "passive"))
    )
    (net (code "55") (name "unconnected-(IC5-Pad2)") (class "Default")
      (node (ref "IC5") (pin "2") (pinfunction "2_2") (pintype "passive"))
    )
    (net (code "56") (name "unconnected-(IC5-Pad3)") (class "Default")
      (node (ref "IC5") (pin "3") (pinfunction "3_3") (pintype "passive"))
    )
    (net (code "57") (name "unconnected-(IC5-Pad4)") (class "Default")
      (node (ref "IC5") (pin "4") (pinfunction "4_4") (pintype "passive"))
    )
    (net (code "58") (name "unconnected-(IC5-Pad5)") (class "Default")
      (node (ref "IC5") (pin "5") (pinfunction "5_5") (pintype "passive"))
    )
    (net (code "59") (name "unconnected-(IC5-Pad7)") (class "Default")
      (node (ref "IC5") (pin "7") (pinfunction "7_7") (pintype "passive"))
    )
    (net (code "60") (name "unconnected-(IC5-Pad8)") (class "Default")
      (node (ref "IC5") (pin "8") (pinfunction "8_8") (pintype "passive"))
    )
    (net (code "61") (name "unconnected-(IC5-Pad9)") (class "Default")
      (node (ref "IC5") (pin "9") (pinfunction "9_9") (pintype "passive"))
    )
    (net (code "62") (name "unconnected-(IC5-Pad10)") (class "Default")
      (node (ref "IC5") (pin "10") (pinfunction "10_10") (pintype "passive"))
    )
    (net (code "63") (name "unconnected-(RESONANCE-Pad3)") (class "Default")
      (node (ref "RESONANCE") (pin "3") (pinfunction "3_3") (pintype "passive"))
    )
    (net (code "64") (name "unconnected-(RESONANCE-Pad4)") (class "Default")
      (node (ref "RESONANCE") (pin "4") (pinfunction "4_4") (pintype "passive"))
    )
    (net (code "65") (name "unconnected-(RESONANCE-Pad5)") (class "Default")
      (node (ref "RESONANCE") (pin "5") (pinfunction "5_5") (pintype "passive"))
    )
    (net (code "66") (name "unconnected-(RESONANCE-Pad6)") (class "Default")
      (node (ref "RESONANCE") (pin "6") (pinfunction "6_6") (pintype "passive"))
    )
    (net (code "67") (name "unconnected-(VCF_CV-Pad4)") (class "Default")
      (node (ref "VCF_CV") (pin "4") (pinfunction "4_4") (pintype "passive"))
    )
    (net (code "68") (name "unconnected-(VCF_CV-Pad5)") (class "Default")
      (node (ref "VCF_CV") (pin "5") (pinfunction "5_5") (pintype "passive"))
    )
    (net (code "69") (name "unconnected-(VCF_CV-Pad6)") (class "Default")
      (node (ref "VCF_CV") (pin "6") (pinfunction "6_6") (pintype "passive"))
    )
    (net (code "70") (name "unconnected-(VCO&VCA_CV1-Pad4)") (class "Default")
      (node (ref "VCO&VCA_CV1") (pin "4") (pinfunction "4_4") (pintype "passive"))
    )
    (net (code "71") (name "unconnected-(VCO&VCA_CV1-Pad5)") (class "Default")
      (node (ref "VCO&VCA_CV1") (pin "5") (pinfunction "5_5") (pintype "passive"))
    )
    (net (code "72") (name "unconnected-(VCO&VCA_CV1-Pad6)") (class "Default")
      (node (ref "VCO&VCA_CV1") (pin "6") (pinfunction "6_6") (pintype "passive"))
    )
    (net (code "73") (name "unconnected-(VCO-PadA)") (class "Default")
      (node (ref "VCO") (pin "A") (pinfunction "A_A") (pintype "passive"))
    )
  )
)
